# SpringReverbRev2_1_SMD.net
KiCad netlist of a schematic drawn in EAGLE
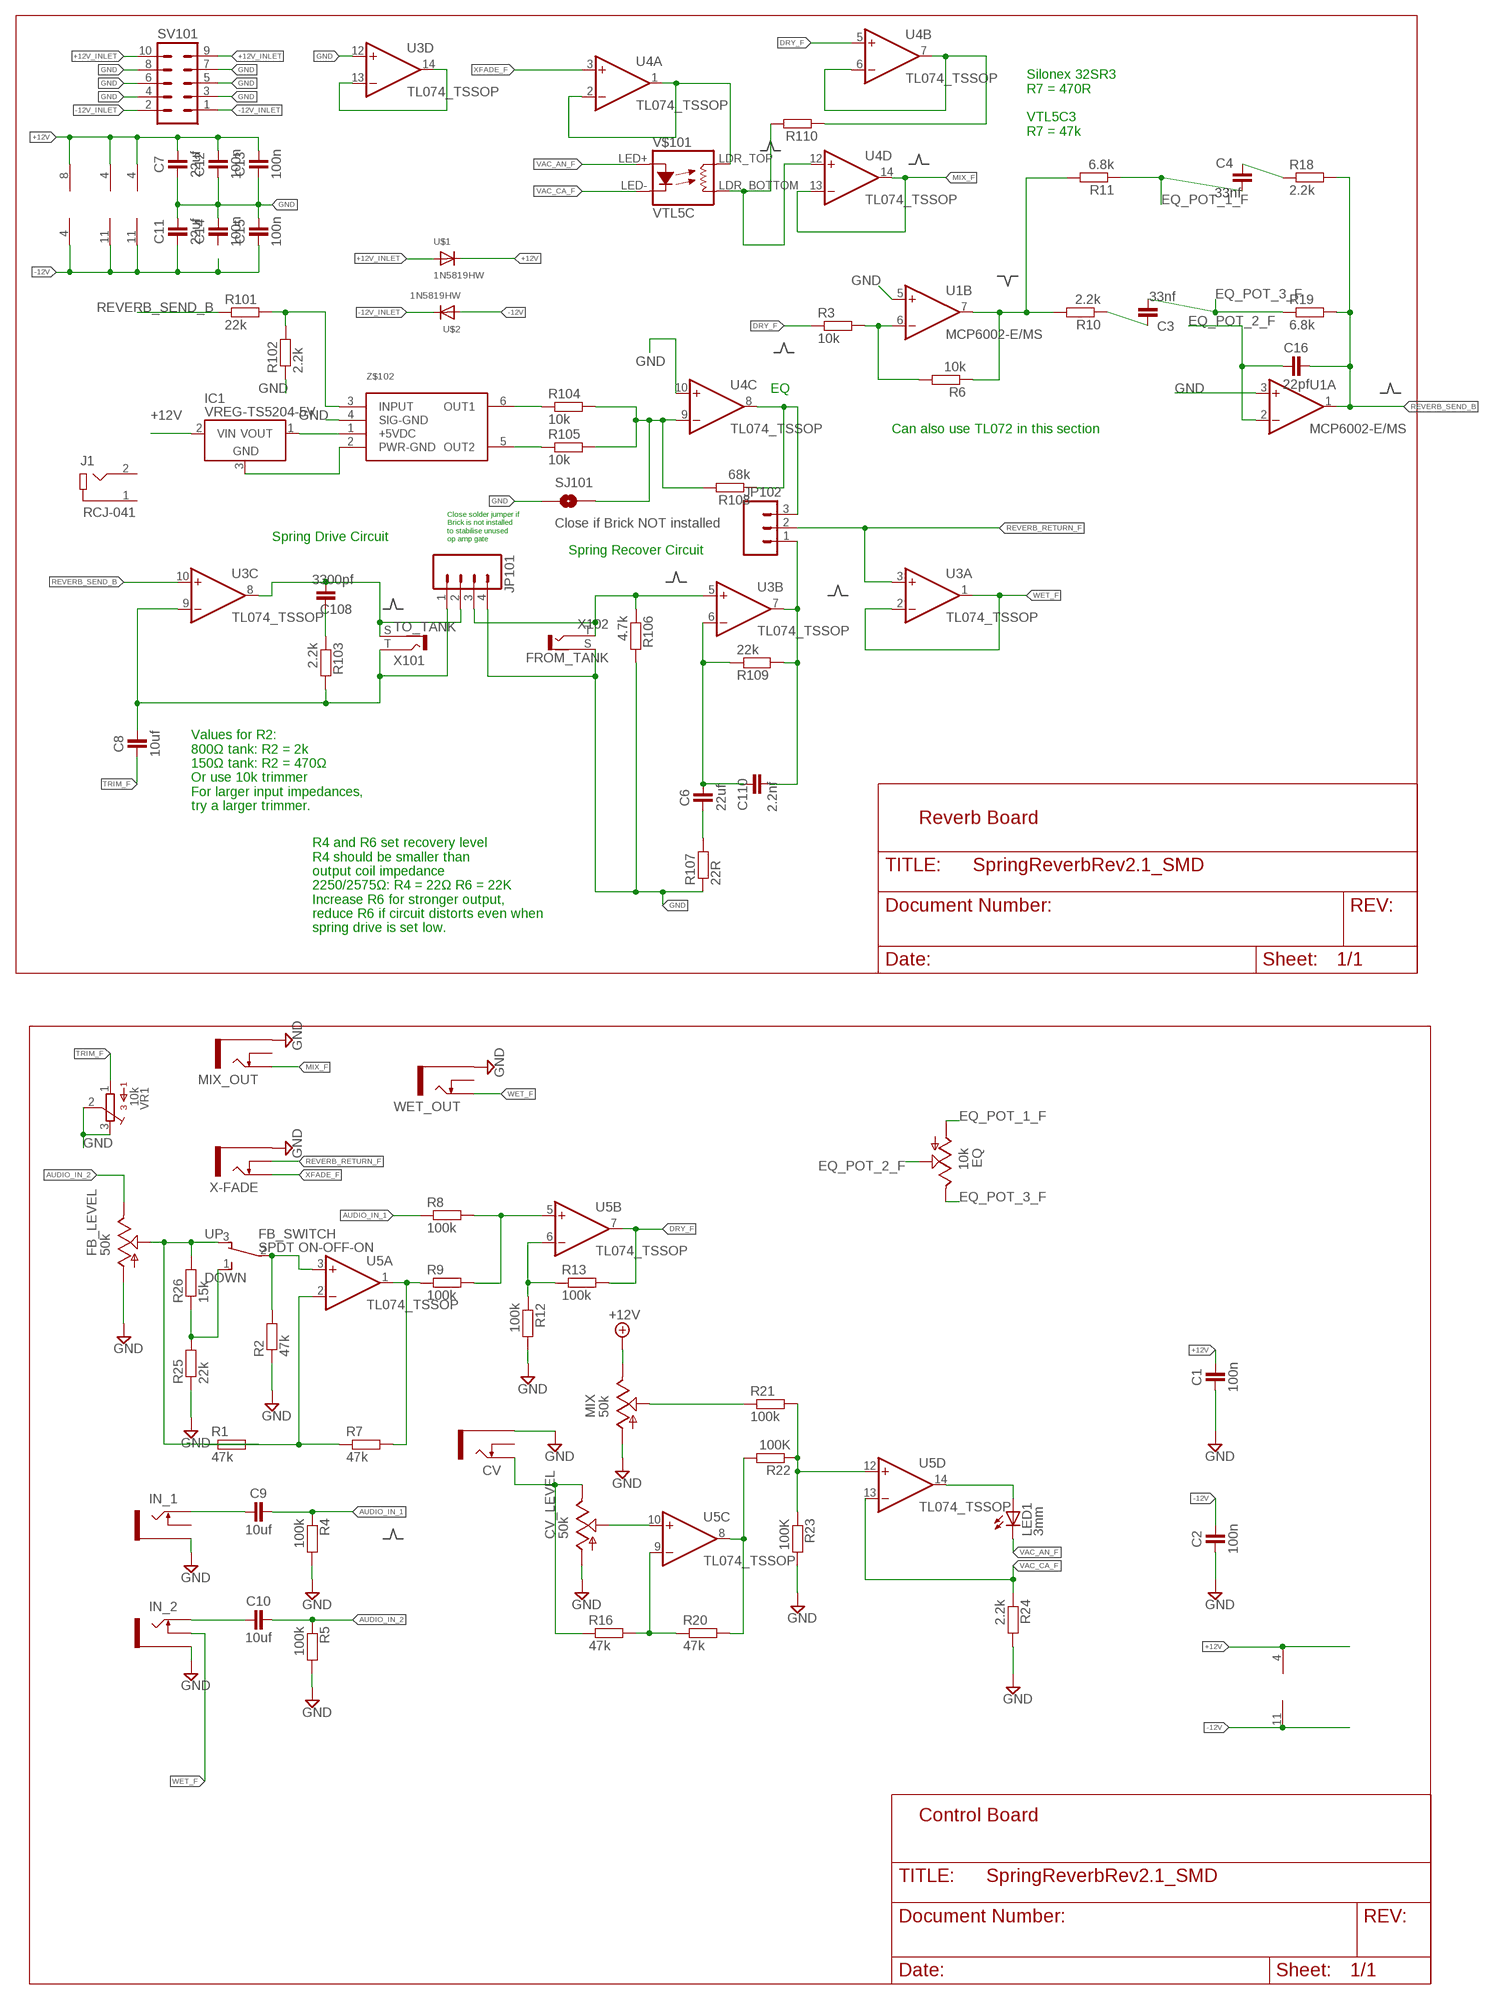
[diagram p0: schematic, sheet 1]

(export (version "E")
  (design (tool "Eeschema 10.0.6"))
  (components
    (comp (ref "C1")
      (value "100n")
      (footprint "eagle-import:C0402")
      (libsource (lib "eagle-import") (part "CAPACITOR-0402"))
    )
    (comp (ref "C2")
      (value "100n")
      (footprint "eagle-import:C0402")
      (libsource (lib "eagle-import") (part "CAPACITOR-0402"))
    )
    (comp (ref "C3")
      (value "33nf")
      (footprint "eagle-import:C0402")
      (libsource (lib "eagle-import") (part "CAPACITOR-0402"))
    )
    (comp (ref "C4")
      (value "33nf")
      (footprint "eagle-import:C0402")
      (libsource (lib "eagle-import") (part "CAPACITOR-0402"))
    )
    (comp (ref "C6")
      (value "22uf")
      (footprint "eagle-import:C1210")
      (libsource (lib "eagle-import") (part "CAPACITOR-1210"))
    )
    (comp (ref "C7")
      (value "22uf")
      (footprint "eagle-import:C1206")
      (libsource (lib "eagle-import") (part "CAPACITOR-1206"))
    )
    (comp (ref "C8")
      (value "10uf")
      (footprint "eagle-import:C0805")
      (libsource (lib "eagle-import") (part "CAPACITOR-0805"))
    )
    (comp (ref "C9")
      (value "10uf")
      (footprint "eagle-import:C0805")
      (libsource (lib "eagle-import") (part "CAPACITOR-0805"))
    )
    (comp (ref "C10")
      (value "10uf")
      (footprint "eagle-import:C0805")
      (libsource (lib "eagle-import") (part "CAPACITOR-0805"))
    )
    (comp (ref "C11")
      (value "22uf")
      (footprint "eagle-import:C1206")
      (libsource (lib "eagle-import") (part "CAPACITOR-1206"))
    )
    (comp (ref "C12")
      (value "100n")
      (footprint "eagle-import:C0402")
      (libsource (lib "eagle-import") (part "CAPACITOR-0402"))
    )
    (comp (ref "C13")
      (value "100n")
      (footprint "eagle-import:C0402")
      (libsource (lib "eagle-import") (part "CAPACITOR-0402"))
    )
    (comp (ref "C14")
      (value "100n")
      (footprint "eagle-import:C0402")
      (libsource (lib "eagle-import") (part "CAPACITOR-0402"))
    )
    (comp (ref "C15")
      (value "100n")
      (footprint "eagle-import:C0402")
      (libsource (lib "eagle-import") (part "CAPACITOR-0402"))
    )
    (comp (ref "C16")
      (value "22pf")
      (footprint "eagle-import:C0402")
      (libsource (lib "eagle-import") (part "CAPACITOR-0402"))
    )
    (comp (ref "C108")
      (value "3300pf")
      (footprint "eagle-import:C0402")
      (libsource (lib "eagle-import") (part "CAPACITOR-0402"))
    )
    (comp (ref "C110")
      (value "2.2nf")
      (footprint "eagle-import:C0402")
      (libsource (lib "eagle-import") (part "CAPACITOR-0402"))
    )
    (comp (ref "CV")
      (value "THONKICONNNEW")
      (footprint "eagle-import:WQP-PJ301M-12_JACK")
      (libsource (lib "eagle-import") (part "THONKICONNNEW"))
    )
    (comp (ref "CV_LEVEL")
      (value "50k")
      (footprint "eagle-import:EVUF")
      (libsource (lib "eagle-import") (part "ALPHA-9MMAF2"))
    )
    (comp (ref "EQ")
      (value "10k")
      (footprint "eagle-import:EVUF")
      (libsource (lib "eagle-import") (part "ALPHA-9MMAF2"))
    )
    (comp (ref "FB_LEVEL")
      (value "50k")
      (footprint "eagle-import:EVUF")
      (libsource (lib "eagle-import") (part "ALPHA-9MMAF2"))
    )
    (comp (ref "FB_SWITCH")
      (value "SPDT ON-OFF-ON")
      (footprint "eagle-import:SPDT-VERTICAL-TOP-SUBMINI-MULTICOMP")
      (libsource (lib "eagle-import") (part "SPDT-VERTICAL-UPTOP-SUBMINI"))
    )
    (comp (ref "IC1")
      (value "VREG-TS5204-5V")
      (footprint "eagle-import:SOT23")
      (libsource (lib "eagle-import") (part "VREG-TS5204-5V"))
    )
    (comp (ref "IN_1")
      (value "THONKICONNNEW")
      (footprint "eagle-import:WQP-PJ301M-12_JACK")
      (libsource (lib "eagle-import") (part "THONKICONNNEW"))
    )
    (comp (ref "IN_2")
      (value "THONKICONNNEW")
      (footprint "eagle-import:WQP-PJ301M-12_JACK")
      (libsource (lib "eagle-import") (part "THONKICONNNEW"))
    )
    (comp (ref "J1")
      (value "RCJ-041")
      (footprint "eagle-import:RCJ-041")
      (fields
        (field (name "DIGIKEY_PART_NUMBER") "CP-1418-ND")
        (field (name "MANUFACTURER") "CUI Inc.")
        (field (name "CREATED_BY") "PCBLayout.com")
      )
      (libsource (lib "eagle-import") (part "RCJ-041"))
    )
    (comp (ref "JP101")
      (value "M04POLAR")
      (footprint "eagle-import:MOLEX-1X4")
      (libsource (lib "eagle-import") (part "M04POLAR"))
    )
    (comp (ref "JP102")
      (value "M03LOCK_NO_SILK")
      (footprint "eagle-import:1X03_LOCK_NO_SILK")
      (libsource (lib "eagle-import") (part "M03LOCK_NO_SILK"))
    )
    (comp (ref "LED1")
      (value "3mm")
      (footprint "eagle-import:LED3MM")
      (libsource (lib "eagle-import") (part "LED3MM"))
    )
    (comp (ref "MIX")
      (value "50k")
      (footprint "eagle-import:EVUF")
      (libsource (lib "eagle-import") (part "ALPHA-9MMAF2"))
    )
    (comp (ref "MIX_OUT")
      (value "THONKICONNNEW")
      (footprint "eagle-import:WQP-PJ301M-12_JACK")
      (libsource (lib "eagle-import") (part "THONKICONNNEW"))
    )
    (comp (ref "R1")
      (value "47k")
      (footprint "eagle-import:C0402")
      (libsource (lib "eagle-import") (part "RESISTOR-0402"))
    )
    (comp (ref "R2")
      (value "47k")
      (footprint "eagle-import:C0402")
      (libsource (lib "eagle-import") (part "RESISTOR-0402"))
    )
    (comp (ref "R3")
      (value "10k")
      (footprint "eagle-import:C0402")
      (libsource (lib "eagle-import") (part "RESISTOR-0402"))
    )
    (comp (ref "R4")
      (value "100k")
      (footprint "eagle-import:C0402")
      (libsource (lib "eagle-import") (part "RESISTOR-0402"))
    )
    (comp (ref "R5")
      (value "100k")
      (footprint "eagle-import:C0402")
      (libsource (lib "eagle-import") (part "RESISTOR-0402"))
    )
    (comp (ref "R6")
      (value "10k")
      (footprint "eagle-import:C0402")
      (libsource (lib "eagle-import") (part "RESISTOR-0402"))
    )
    (comp (ref "R7")
      (value "47k")
      (footprint "eagle-import:C0402")
      (libsource (lib "eagle-import") (part "RESISTOR-0402"))
    )
    (comp (ref "R8")
      (value "100k")
      (footprint "eagle-import:C0402")
      (libsource (lib "eagle-import") (part "RESISTOR-0402"))
    )
    (comp (ref "R9")
      (value "100k")
      (footprint "eagle-import:C0402")
      (libsource (lib "eagle-import") (part "RESISTOR-0402"))
    )
    (comp (ref "R10")
      (value "2.2k")
      (footprint "eagle-import:C0402")
      (libsource (lib "eagle-import") (part "RESISTOR-0402"))
    )
    (comp (ref "R11")
      (value "6.8k")
      (footprint "eagle-import:C0402")
      (libsource (lib "eagle-import") (part "RESISTOR-0402"))
    )
    (comp (ref "R12")
      (value "100k")
      (footprint "eagle-import:C0402")
      (libsource (lib "eagle-import") (part "RESISTOR-0402"))
    )
    (comp (ref "R13")
      (value "100k")
      (footprint "eagle-import:C0402")
      (libsource (lib "eagle-import") (part "RESISTOR-0402"))
    )
    (comp (ref "R16")
      (value "47k")
      (footprint "eagle-import:C0402")
      (libsource (lib "eagle-import") (part "RESISTOR-0402"))
    )
    (comp (ref "R18")
      (value "2.2k")
      (footprint "eagle-import:C0402")
      (libsource (lib "eagle-import") (part "RESISTOR-0402"))
    )
    (comp (ref "R19")
      (value "6.8k")
      (footprint "eagle-import:C0402")
      (libsource (lib "eagle-import") (part "RESISTOR-0402"))
    )
    (comp (ref "R20")
      (value "47k")
      (footprint "eagle-import:C0402")
      (libsource (lib "eagle-import") (part "RESISTOR-0402"))
    )
    (comp (ref "R21")
      (value "100k")
      (footprint "eagle-import:C0402")
      (libsource (lib "eagle-import") (part "RESISTOR-0402"))
    )
    (comp (ref "R22")
      (value "100K")
      (footprint "eagle-import:C0402")
      (libsource (lib "eagle-import") (part "RESISTOR-0402"))
    )
    (comp (ref "R23")
      (value "100K")
      (footprint "eagle-import:C0402")
      (libsource (lib "eagle-import") (part "RESISTOR-0402"))
    )
    (comp (ref "R24")
      (value "2.2k")
      (footprint "eagle-import:C0402")
      (libsource (lib "eagle-import") (part "RESISTOR-0402"))
    )
    (comp (ref "R25")
      (value "22k")
      (footprint "eagle-import:C0402")
      (libsource (lib "eagle-import") (part "RESISTOR-0402"))
    )
    (comp (ref "R26")
      (value "15k")
      (footprint "eagle-import:C0402")
      (libsource (lib "eagle-import") (part "RESISTOR-0402"))
    )
    (comp (ref "R101")
      (value "22k")
      (footprint "eagle-import:C0402")
      (libsource (lib "eagle-import") (part "RESISTOR-0402"))
    )
    (comp (ref "R102")
      (value "2.2k")
      (footprint "eagle-import:C0402")
      (libsource (lib "eagle-import") (part "RESISTOR-0402"))
    )
    (comp (ref "R103")
      (value "2.2k")
      (footprint "eagle-import:C0402")
      (libsource (lib "eagle-import") (part "RESISTOR-0402"))
    )
    (comp (ref "R104")
      (value "10k")
      (footprint "eagle-import:C0402")
      (libsource (lib "eagle-import") (part "RESISTOR-0402"))
    )
    (comp (ref "R105")
      (value "10k")
      (footprint "eagle-import:C0402")
      (libsource (lib "eagle-import") (part "RESISTOR-0402"))
    )
    (comp (ref "R106")
      (value "4.7k")
      (footprint "eagle-import:C0402")
      (libsource (lib "eagle-import") (part "RESISTOR-0402"))
    )
    (comp (ref "R107")
      (value "22R")
      (footprint "eagle-import:C0402")
      (libsource (lib "eagle-import") (part "RESISTOR-0402"))
    )
    (comp (ref "R108")
      (value "68k")
      (footprint "eagle-import:C0402")
      (libsource (lib "eagle-import") (part "RESISTOR-0402"))
    )
    (comp (ref "R109")
      (value "22k")
      (footprint "eagle-import:C0402")
      (libsource (lib "eagle-import") (part "RESISTOR-0402"))
    )
    (comp (ref "R110")
      (value "RESISTOR-0402")
      (footprint "eagle-import:C0402")
      (libsource (lib "eagle-import") (part "RESISTOR-0402"))
    )
    (comp (ref "SJ101")
      (value "Close if Brick NOT installed")
      (footprint "eagle-import:SJ_2S-NOTRACE")
      (libsource (lib "eagle-import") (part "SOLDERJUMPERNC2"))
    )
    (comp (ref "SV101")
      (value "10_PIN_HEADER")
      (footprint "eagle-import:MA05-2")
      (libsource (lib "eagle-import") (part "10_PIN_HEADER"))
    )
    (comp (ref "U$1")
      (value "1N5819HW")
      (footprint "eagle-import:SOD-123-EDITED")
      (libsource (lib "eagle-import") (part "1N5819HW"))
    )
    (comp (ref "U$2")
      (value "1N5819HW")
      (footprint "eagle-import:SOD-123-EDITED")
      (libsource (lib "eagle-import") (part "1N5819HW"))
    )
    (comp (ref "U1")
      (value "MCP6002-E/MS")
      (footprint "eagle-import:SOP65P490X110-8N")
      (libsource (lib "eagle-import") (part "MCP6002-E/MS"))
    )
    (comp (ref "U3")
      (value "TL074_TSSOP")
      (footprint "eagle-import:SOP65P640X120-14N")
      (fields (field (name "MPN") "MCP6004-I/ST"))
      (libsource (lib "eagle-import") (part "LM324_TSSOP"))
    )
    (comp (ref "U4")
      (value "TL074_TSSOP")
      (footprint "eagle-import:SOP65P640X120-14N")
      (fields (field (name "MPN") "MCP6004-I/ST"))
      (libsource (lib "eagle-import") (part "LM324_TSSOP"))
    )
    (comp (ref "U5")
      (value "TL074_TSSOP")
      (footprint "eagle-import:SOP65P640X120-14N")
      (fields (field (name "MPN") "MCP6004-I/ST"))
      (libsource (lib "eagle-import") (part "LM324_TSSOP"))
    )
    (comp (ref "V$101")
      (value "VTL5C")
      (footprint "eagle-import:VACTROL_COMPACT")
      (libsource (lib "eagle-import") (part "VACTROL_COMPACT"))
    )
    (comp (ref "VR1")
      (value "10k")
      (footprint "eagle-import:BOURNS_3362P_TRIMMER")
      (libsource (lib "eagle-import") (part "BOURNS_3362P_TRIMMERP"))
    )
    (comp (ref "WET_OUT")
      (value "THONKICONNNEW")
      (footprint "eagle-import:WQP-PJ301M-12_JACK")
      (libsource (lib "eagle-import") (part "THONKICONNNEW"))
    )
    (comp (ref "X-FADE")
      (value "THONKICONNNEW")
      (footprint "eagle-import:WQP-PJ301M-12_JACK")
      (libsource (lib "eagle-import") (part "THONKICONNNEW"))
    )
    (comp (ref "X101")
      (value "TO_TANK")
      (footprint "eagle-import:BTOR1")
      (fields (field (name "MPN") "BTOR 1"))
      (libsource (lib "eagle-import") (part "BTOR1"))
    )
    (comp (ref "X102")
      (value "FROM_TANK")
      (footprint "eagle-import:BTOR1")
      (fields (field (name "MPN") "BTOR 1"))
      (libsource (lib "eagle-import") (part "BTOR1"))
    )
    (comp (ref "Z$102")
      (value "BTDR-2H")
      (footprint "eagle-import:BTDR-2H")
      (libsource (lib "eagle-import") (part "BTDR-2H"))
    )
  )
  (nets
    (net (code "1") (name "+12V") (class "Default")
      (node (ref "C1") (pin "2") (pinfunction "2_2") (pintype "passive"))
      (node (ref "C12") (pin "2") (pinfunction "2_2") (pintype "passive"))
      (node (ref "C13") (pin "2") (pinfunction "2_2") (pintype "passive"))
      (node (ref "C7") (pin "2") (pinfunction "2_2") (pintype "passive"))
      (node (ref "IC1") (pin "2") (pinfunction "VIN_2") (pintype "power_in"))
      (node (ref "MIX") (pin "3") (pinfunction "E_3") (pintype "passive"))
      (node (ref "U$1") (pin "C") (pinfunction "C_C") (pintype "passive"))
      (node (ref "U1") (pin "8") (pinfunction "V+_8") (pintype "power_in"))
      (node (ref "U3") (pin "4") (pinfunction "V+_4") (pintype "power_in"))
      (node (ref "U4") (pin "4") (pinfunction "V+_4") (pintype "power_in"))
      (node (ref "U5") (pin "4") (pinfunction "V+_4") (pintype "power_in"))
    )
    (net (code "2") (name "+12V_INLET") (class "Default")
      (node (ref "SV101") (pin "10") (pinfunction "10_10") (pintype "passive"))
      (node (ref "SV101") (pin "9") (pinfunction "9_9") (pintype "passive"))
      (node (ref "U$1") (pin "A") (pinfunction "A_A") (pintype "passive"))
    )
    (net (code "3") (name "-12V") (class "Default")
      (node (ref "C11") (pin "1") (pinfunction "1_1") (pintype "passive"))
      (node (ref "C15") (pin "1") (pinfunction "1_1") (pintype "passive"))
      (node (ref "C2") (pin "2") (pinfunction "2_2") (pintype "passive"))
      (node (ref "U$2") (pin "A") (pinfunction "A_A") (pintype "passive"))
      (node (ref "U1") (pin "4") (pinfunction "V-_4") (pintype "power_in"))
      (node (ref "U3") (pin "11") (pinfunction "V-_11") (pintype "power_in"))
      (node (ref "U4") (pin "11") (pinfunction "V-_11") (pintype "power_in"))
      (node (ref "U5") (pin "11") (pinfunction "V-_11") (pintype "power_in"))
    )
    (net (code "4") (name "-12V_INLET") (class "Default")
      (node (ref "SV101") (pin "1") (pinfunction "1_1") (pintype "passive"))
      (node (ref "SV101") (pin "2") (pinfunction "2_2") (pintype "passive"))
      (node (ref "U$2") (pin "C") (pinfunction "C_C") (pintype "passive"))
    )
    (net (code "5") (name "/EQ_POT_1_F") (class "Default")
      (node (ref "C4") (pin "2") (pinfunction "2_2") (pintype "passive"))
      (node (ref "EQ") (pin "1") (pinfunction "A_1") (pintype "passive"))
      (node (ref "R11") (pin "1") (pinfunction "1_1") (pintype "passive"))
    )
    (net (code "6") (name "/EQ_POT_2_F") (class "Default")
      (node (ref "C16") (pin "1") (pinfunction "1_1") (pintype "passive"))
      (node (ref "EQ") (pin "2") (pinfunction "S_2") (pintype "passive"))
      (node (ref "U1") (pin "2") (pinfunction "-IN_2") (pintype "input"))
    )
    (net (code "7") (name "/EQ_POT_3_F") (class "Default")
      (node (ref "C3") (pin "2") (pinfunction "2_2") (pintype "passive"))
      (node (ref "EQ") (pin "3") (pinfunction "E_3") (pintype "passive"))
      (node (ref "R19") (pin "1") (pinfunction "1_1") (pintype "passive"))
    )
    (net (code "8") (name "AUDIO_IN_1") (class "Default")
      (node (ref "C9") (pin "2") (pinfunction "2_2") (pintype "passive"))
      (node (ref "R4") (pin "1") (pinfunction "1_1") (pintype "passive"))
      (node (ref "R8") (pin "1") (pinfunction "1_1") (pintype "passive"))
    )
    (net (code "9") (name "AUDIO_IN_2") (class "Default")
      (node (ref "C10") (pin "2") (pinfunction "2_2") (pintype "passive"))
      (node (ref "FB_LEVEL") (pin "3") (pinfunction "E_3") (pintype "passive"))
      (node (ref "R5") (pin "1") (pinfunction "1_1") (pintype "passive"))
    )
    (net (code "10") (name "DRY_F") (class "Default")
      (node (ref "R13") (pin "2") (pinfunction "2_2") (pintype "passive"))
      (node (ref "R3") (pin "1") (pinfunction "1_1") (pintype "passive"))
      (node (ref "U4") (pin "5") (pinfunction "+IN_5") (pintype "input"))
      (node (ref "U5") (pin "7") (pinfunction "OUT_7") (pintype "output"))
    )
    (net (code "11") (name "GND") (class "Default")
      (node (ref "C1") (pin "1") (pinfunction "1_1") (pintype "passive"))
      (node (ref "C11") (pin "2") (pinfunction "2_2") (pintype "passive"))
      (node (ref "C12") (pin "1") (pinfunction "1_1") (pintype "passive"))
      (node (ref "C13") (pin "1") (pinfunction "1_1") (pintype "passive"))
      (node (ref "C14") (pin "2") (pinfunction "2_2") (pintype "passive"))
      (node (ref "C15") (pin "2") (pinfunction "2_2") (pintype "passive"))
      (node (ref "C2") (pin "1") (pinfunction "1_1") (pintype "passive"))
      (node (ref "C7") (pin "1") (pinfunction "1_1") (pintype "passive"))
      (node (ref "CV") (pin "P$3_SLEEVE") (pinfunction "SLEEVE_P$3_SLEEVE") (pintype "passive"))
      (node (ref "CV_LEVEL") (pin "1") (pinfunction "A_1") (pintype "passive"))
      (node (ref "FB_LEVEL") (pin "1") (pinfunction "A_1") (pintype "passive"))
      (node (ref "IN_1") (pin "P$3_SLEEVE") (pinfunction "SLEEVE_P$3_SLEEVE") (pintype "passive"))
      (node (ref "IN_2") (pin "P$3_SLEEVE") (pinfunction "SLEEVE_P$3_SLEEVE") (pintype "passive"))
      (node (ref "JP101") (pin "4") (pinfunction "4_4") (pintype "passive"))
      (node (ref "MIX") (pin "1") (pinfunction "A_1") (pintype "passive"))
      (node (ref "MIX_OUT") (pin "P$3_SLEEVE") (pinfunction "SLEEVE_P$3_SLEEVE") (pintype "passive"))
      (node (ref "R102") (pin "1") (pinfunction "1_1") (pintype "passive"))
      (node (ref "R106") (pin "2") (pinfunction "2_2") (pintype "passive"))
      (node (ref "R107") (pin "1") (pinfunction "1_1") (pintype "passive"))
      (node (ref "R12") (pin "2") (pinfunction "2_2") (pintype "passive"))
      (node (ref "R2") (pin "1") (pinfunction "1_1") (pintype "passive"))
      (node (ref "R23") (pin "2") (pinfunction "2_2") (pintype "passive"))
      (node (ref "R24") (pin "2") (pinfunction "2_2") (pintype "passive"))
      (node (ref "R25") (pin "1") (pinfunction "1_1") (pintype "passive"))
      (node (ref "R4") (pin "2") (pinfunction "2_2") (pintype "passive"))
      (node (ref "R5") (pin "2") (pinfunction "2_2") (pintype "passive"))
      (node (ref "SJ101") (pin "1") (pinfunction "1_1") (pintype "passive"))
      (node (ref "SV101") (pin "3") (pinfunction "3_3") (pintype "passive"))
      (node (ref "SV101") (pin "4") (pinfunction "4_4") (pintype "passive"))
      (node (ref "SV101") (pin "5") (pinfunction "5_5") (pintype "passive"))
      (node (ref "SV101") (pin "6") (pinfunction "6_6") (pintype "passive"))
      (node (ref "SV101") (pin "7") (pinfunction "7_7") (pintype "passive"))
      (node (ref "SV101") (pin "8") (pinfunction "8_8") (pintype "passive"))
      (node (ref "U1") (pin "3") (pinfunction "+IN_3") (pintype "input"))
      (node (ref "U1") (pin "5") (pinfunction "+IN_5") (pintype "input"))
      (node (ref "U3") (pin "12") (pinfunction "+IN_12") (pintype "input"))
      (node (ref "U4") (pin "10") (pinfunction "+IN_10") (pintype "input"))
      (node (ref "VR1") (pin "2") (pinfunction "2_2") (pintype "passive"))
      (node (ref "VR1") (pin "3") (pinfunction "3_3") (pintype "passive"))
      (node (ref "WET_OUT") (pin "P$3_SLEEVE") (pinfunction "SLEEVE_P$3_SLEEVE") (pintype "passive"))
      (node (ref "X-FADE") (pin "P$3_SLEEVE") (pinfunction "SLEEVE_P$3_SLEEVE") (pintype "passive"))
      (node (ref "X102") (pin "S") (pinfunction "2_S") (pintype "passive"))
      (node (ref "Z$102") (pin "4") (pinfunction "SIG-GND_4") (pintype "bidirectional"))
    )
    (net (code "12") (name "MIX_F") (class "Default")
      (node (ref "MIX_OUT") (pin "P$1_TIP") (pinfunction "TIP_P$1_TIP") (pintype "passive"))
      (node (ref "U4") (pin "13") (pinfunction "-IN_13") (pintype "input"))
      (node (ref "U4") (pin "14") (pinfunction "OUT_14") (pintype "output"))
    )
    (net (code "13") (name "Net-(C3-Pad1)") (class "Default")
      (node (ref "C3") (pin "1") (pinfunction "1_1") (pintype "passive"))
      (node (ref "R10") (pin "1") (pinfunction "1_1") (pintype "passive"))
    )
    (net (code "14") (name "Net-(C4-Pad1)") (class "Default")
      (node (ref "C4") (pin "1") (pinfunction "1_1") (pintype "passive"))
      (node (ref "R18") (pin "1") (pinfunction "1_1") (pintype "passive"))
    )
    (net (code "15") (name "Net-(C6-Pad1)") (class "Default")
      (node (ref "C6") (pin "1") (pinfunction "1_1") (pintype "passive"))
      (node (ref "R107") (pin "2") (pinfunction "2_2") (pintype "passive"))
    )
    (net (code "16") (name "Net-(C108-Pad1)") (class "Default")
      (node (ref "C108") (pin "1") (pinfunction "1_1") (pintype "passive"))
      (node (ref "R103") (pin "1") (pinfunction "1_1") (pintype "passive"))
    )
    (net (code "17") (name "Net-(CV-TIP)") (class "Default")
      (node (ref "CV") (pin "P$1_TIP") (pinfunction "TIP_P$1_TIP") (pintype "passive"))
      (node (ref "CV_LEVEL") (pin "3") (pinfunction "E_3") (pintype "passive"))
      (node (ref "R16") (pin "1") (pinfunction "1_1") (pintype "passive"))
    )
    (net (code "18") (name "Net-(CV_LEVEL-S)") (class "Default")
      (node (ref "CV_LEVEL") (pin "2") (pinfunction "S_2") (pintype "passive"))
      (node (ref "U5") (pin "10") (pinfunction "+IN_10") (pintype "input"))
    )
    (net (code "19") (name "Net-(FB_LEVEL-S)") (class "Default")
      (node (ref "FB_LEVEL") (pin "2") (pinfunction "S_2") (pintype "passive"))
      (node (ref "FB_SWITCH") (pin "3") (pinfunction "3_3") (pintype "passive"))
      (node (ref "R1") (pin "2") (pinfunction "2_2") (pintype "passive"))
      (node (ref "R26") (pin "2") (pinfunction "2_2") (pintype "passive"))
    )
    (net (code "20") (name "Net-(FB_SWITCH-Pad1)") (class "Default")
      (node (ref "FB_SWITCH") (pin "1") (pinfunction "1_1") (pintype "passive"))
      (node (ref "R25") (pin "2") (pinfunction "2_2") (pintype "passive"))
      (node (ref "R26") (pin "1") (pinfunction "1_1") (pintype "passive"))
    )
    (net (code "21") (name "Net-(IC1-GND)") (class "Default")
      (node (ref "IC1") (pin "3") (pinfunction "GND_3") (pintype "power_in"))
      (node (ref "Z$102") (pin "2") (pinfunction "PWR-GND_2") (pintype "bidirectional"))
    )
    (net (code "22") (name "Net-(IC1-VOUT)") (class "Default")
      (node (ref "IC1") (pin "1") (pinfunction "VOUT_1") (pintype "power_in"))
      (node (ref "Z$102") (pin "1") (pinfunction "+5VDC_1") (pintype "bidirectional"))
    )
    (net (code "23") (name "Net-(IN_1-TIP)") (class "Default")
      (node (ref "C9") (pin "1") (pinfunction "1_1") (pintype "passive"))
      (node (ref "IN_1") (pin "P$1_TIP") (pinfunction "TIP_P$1_TIP") (pintype "passive"))
    )
    (net (code "24") (name "Net-(IN_2-TIP)") (class "Default")
      (node (ref "C10") (pin "1") (pinfunction "1_1") (pintype "passive"))
      (node (ref "IN_2") (pin "P$1_TIP") (pinfunction "TIP_P$1_TIP") (pintype "passive"))
    )
    (net (code "25") (name "Net-(MIX-S)") (class "Default")
      (node (ref "MIX") (pin "2") (pinfunction "S_2") (pintype "passive"))
      (node (ref "R21") (pin "1") (pinfunction "1_1") (pintype "passive"))
    )
    (net (code "26") (name "Net-(U1B--IN)") (class "Default")
      (node (ref "R3") (pin "2") (pinfunction "2_2") (pintype "passive"))
      (node (ref "R6") (pin "2") (pinfunction "2_2") (pintype "passive"))
      (node (ref "U1") (pin "6") (pinfunction "-IN_6") (pintype "input"))
    )
    (net (code "27") (name "Net-(U1B-OUT)") (class "Default")
      (node (ref "R10") (pin "2") (pinfunction "2_2") (pintype "passive"))
      (node (ref "R11") (pin "2") (pinfunction "2_2") (pintype "passive"))
      (node (ref "R6") (pin "1") (pinfunction "1_1") (pintype "passive"))
      (node (ref "U1") (pin "7") (pinfunction "OUT_7") (pintype "output"))
    )
    (net (code "28") (name "Net-(U3B-+IN)") (class "Default")
      (node (ref "JP101") (pin "3") (pinfunction "3_3") (pintype "passive"))
      (node (ref "R106") (pin "1") (pinfunction "1_1") (pintype "passive"))
      (node (ref "U3") (pin "5") (pinfunction "+IN_5") (pintype "input"))
      (node (ref "X102") (pin "T") (pinfunction "1_T") (pintype "passive"))
    )
    (net (code "29") (name "Net-(U3B--IN)") (class "Default")
      (node (ref "C110") (pin "1") (pinfunction "1_1") (pintype "passive"))
      (node (ref "C6") (pin "2") (pinfunction "2_2") (pintype "passive"))
      (node (ref "R109") (pin "1") (pinfunction "1_1") (pintype "passive"))
      (node (ref "U3") (pin "6") (pinfunction "-IN_6") (pintype "input"))
    )
    (net (code "30") (name "Net-(U3B-OUT)") (class "Default")
      (node (ref "C110") (pin "2") (pinfunction "2_2") (pintype "passive"))
      (node (ref "JP102") (pin "1") (pinfunction "1_1") (pintype "passive"))
      (node (ref "R109") (pin "2") (pinfunction "2_2") (pintype "passive"))
      (node (ref "U3") (pin "7") (pinfunction "OUT_7") (pintype "output"))
    )
    (net (code "31") (name "Net-(U3C--IN)") (class "Default")
      (node (ref "C8") (pin "2") (pinfunction "2_2") (pintype "passive"))
      (node (ref "JP101") (pin "1") (pinfunction "1_1") (pintype "passive"))
      (node (ref "R103") (pin "2") (pinfunction "2_2") (pintype "passive"))
      (node (ref "U3") (pin "9") (pinfunction "-IN_9") (pintype "input"))
      (node (ref "X101") (pin "T") (pinfunction "1_T") (pintype "passive"))
    )
    (net (code "32") (name "Net-(U3C-OUT)") (class "Default")
      (node (ref "C108") (pin "2") (pinfunction "2_2") (pintype "passive"))
      (node (ref "JP101") (pin "2") (pinfunction "2_2") (pintype "passive"))
      (node (ref "U3") (pin "8") (pinfunction "OUT_8") (pintype "output"))
      (node (ref "X101") (pin "S") (pinfunction "2_S") (pintype "passive"))
    )
    (net (code "33") (name "Net-(U3D--IN)") (class "Default")
      (node (ref "U3") (pin "13") (pinfunction "-IN_13") (pintype "input"))
      (node (ref "U3") (pin "14") (pinfunction "OUT_14") (pintype "output"))
    )
    (net (code "34") (name "Net-(U4A--IN)") (class "Default")
      (node (ref "U4") (pin "1") (pinfunction "OUT_1") (pintype "output"))
      (node (ref "U4") (pin "2") (pinfunction "-IN_2") (pintype "input"))
      (node (ref "V$101") (pin "LDR_TOP") (pinfunction "RES1_LDR_TOP") (pintype "passive"))
    )
    (net (code "35") (name "Net-(U4B--IN)") (class "Default")
      (node (ref "R110") (pin "1") (pinfunction "1_1") (pintype "passive"))
      (node (ref "U4") (pin "6") (pinfunction "-IN_6") (pintype "input"))
      (node (ref "U4") (pin "7") (pinfunction "OUT_7") (pintype "output"))
    )
    (net (code "36") (name "Net-(U4C--IN)") (class "Default")
      (node (ref "R104") (pin "2") (pinfunction "2_2") (pintype "passive"))
      (node (ref "R105") (pin "2") (pinfunction "2_2") (pintype "passive"))
      (node (ref "R108") (pin "2") (pinfunction "2_2") (pintype "passive"))
      (node (ref "SJ101") (pin "2") (pinfunction "2_2") (pintype "passive"))
      (node (ref "U4") (pin "9") (pinfunction "-IN_9") (pintype "input"))
    )
    (net (code "37") (name "Net-(U4C-OUT)") (class "Default")
      (node (ref "JP102") (pin "3") (pinfunction "3_3") (pintype "passive"))
      (node (ref "R108") (pin "1") (pinfunction "1_1") (pintype "passive"))
      (node (ref "U4") (pin "8") (pinfunction "OUT_8") (pintype "output"))
    )
    (net (code "38") (name "Net-(U4D-+IN)") (class "Default")
      (node (ref "R110") (pin "2") (pinfunction "2_2") (pintype "passive"))
      (node (ref "U4") (pin "12") (pinfunction "+IN_12") (pintype "input"))
      (node (ref "V$101") (pin "LDR_BOTTOM") (pinfunction "RES2_LDR_BOTTOM") (pintype "passive"))
    )
    (net (code "39") (name "Net-(U5A-+IN)") (class "Default")
      (node (ref "FB_SWITCH") (pin "2") (pinfunction "2_2") (pintype "passive"))
      (node (ref "R2") (pin "2") (pinfunction "2_2") (pintype "passive"))
      (node (ref "U5") (pin "3") (pinfunction "+IN_3") (pintype "input"))
    )
    (net (code "40") (name "Net-(U5A--IN)") (class "Default")
      (node (ref "R1") (pin "1") (pinfunction "1_1") (pintype "passive"))
      (node (ref "R7") (pin "1") (pinfunction "1_1") (pintype "passive"))
      (node (ref "U5") (pin "2") (pinfunction "-IN_2") (pintype "input"))
    )
    (net (code "41") (name "Net-(U5A-OUT)") (class "Default")
      (node (ref "R7") (pin "2") (pinfunction "2_2") (pintype "passive"))
      (node (ref "R9") (pin "1") (pinfunction "1_1") (pintype "passive"))
      (node (ref "U5") (pin "1") (pinfunction "OUT_1") (pintype "output"))
    )
    (net (code "42") (name "Net-(U5B-+IN)") (class "Default")
      (node (ref "R8") (pin "2") (pinfunction "2_2") (pintype "passive"))
      (node (ref "R9") (pin "2") (pinfunction "2_2") (pintype "passive"))
      (node (ref "U5") (pin "5") (pinfunction "+IN_5") (pintype "input"))
    )
    (net (code "43") (name "Net-(U5B--IN)") (class "Default")
      (node (ref "R12") (pin "1") (pinfunction "1_1") (pintype "passive"))
      (node (ref "R13") (pin "1") (pinfunction "1_1") (pintype "passive"))
      (node (ref "U5") (pin "6") (pinfunction "-IN_6") (pintype "input"))
    )
    (net (code "44") (name "Net-(U5C--IN)") (class "Default")
      (node (ref "R16") (pin "2") (pinfunction "2_2") (pintype "passive"))
      (node (ref "R20") (pin "1") (pinfunction "1_1") (pintype "passive"))
      (node (ref "U5") (pin "9") (pinfunction "-IN_9") (pintype "input"))
    )
    (net (code "45") (name "Net-(U5C-OUT)") (class "Default")
      (node (ref "R20") (pin "2") (pinfunction "2_2") (pintype "passive"))
      (node (ref "R22") (pin "2") (pinfunction "2_2") (pintype "passive"))
      (node (ref "U5") (pin "8") (pinfunction "OUT_8") (pintype "output"))
    )
    (net (code "46") (name "Net-(U5D-+IN)") (class "Default")
      (node (ref "R21") (pin "2") (pinfunction "2_2") (pintype "passive"))
      (node (ref "R22") (pin "1") (pinfunction "1_1") (pintype "passive"))
      (node (ref "R23") (pin "1") (pinfunction "1_1") (pintype "passive"))
      (node (ref "U5") (pin "12") (pinfunction "+IN_12") (pintype "input"))
    )
    (net (code "47") (name "Net-(U5D-OUT)") (class "Default")
      (node (ref "LED1") (pin "A") (pinfunction "A_A") (pintype "passive"))
      (node (ref "U5") (pin "14") (pinfunction "OUT_14") (pintype "output"))
    )
    (net (code "48") (name "Net-(Z$102-INPUT)") (class "Default")
      (node (ref "R101") (pin "2") (pinfunction "2_2") (pintype "passive"))
      (node (ref "R102") (pin "2") (pinfunction "2_2") (pintype "passive"))
      (node (ref "Z$102") (pin "3") (pinfunction "INPUT_3") (pintype "bidirectional"))
    )
    (net (code "49") (name "Net-(Z$102-OUT1)") (class "Default")
      (node (ref "R104") (pin "1") (pinfunction "1_1") (pintype "passive"))
      (node (ref "Z$102") (pin "6") (pinfunction "OUT1_6") (pintype "bidirectional"))
    )
    (net (code "50") (name "Net-(Z$102-OUT2)") (class "Default")
      (node (ref "R105") (pin "1") (pinfunction "1_1") (pintype "passive"))
      (node (ref "Z$102") (pin "5") (pinfunction "OUT2_5") (pintype "bidirectional"))
    )
    (net (code "51") (name "REVERB_RETURN_F") (class "Default")
      (node (ref "JP102") (pin "2") (pinfunction "2_2") (pintype "passive"))
      (node (ref "U3") (pin "3") (pinfunction "+IN_3") (pintype "input"))
      (node (ref "X-FADE") (pin "P$2_SWITCH") (pinfunction "SWITCH_P$2_SWITCH") (pintype "passive"))
    )
    (net (code "52") (name "REVERB_SEND_B") (class "Default")
      (node (ref "C16") (pin "2") (pinfunction "2_2") (pintype "passive"))
      (node (ref "R101") (pin "1") (pinfunction "1_1") (pintype "passive"))
      (node (ref "R18") (pin "2") (pinfunction "2_2") (pintype "passive"))
      (node (ref "R19") (pin "2") (pinfunction "2_2") (pintype "passive"))
      (node (ref "U1") (pin "1") (pinfunction "OUT_1") (pintype "output"))
      (node (ref "U3") (pin "10") (pinfunction "+IN_10") (pintype "input"))
    )
    (net (code "53") (name "TRIM_F") (class "Default")
      (node (ref "C8") (pin "1") (pinfunction "1_1") (pintype "passive"))
      (node (ref "VR1") (pin "1") (pinfunction "1_1") (pintype "passive"))
    )
    (net (code "54") (name "VAC_AN_F") (class "Default")
      (node (ref "LED1") (pin "K") (pinfunction "C_K") (pintype "passive"))
      (node (ref "V$101") (pin "LED+") (pinfunction "LED+_LED+") (pintype "passive"))
    )
    (net (code "55") (name "VAC_CA_F") (class "Default")
      (node (ref "R24") (pin "1") (pinfunction "1_1") (pintype "passive"))
      (node (ref "U5") (pin "13") (pinfunction "-IN_13") (pintype "input"))
      (node (ref "V$101") (pin "LED-") (pinfunction "LED-_LED-") (pintype "passive"))
    )
    (net (code "56") (name "WET_F") (class "Default")
      (node (ref "IN_2") (pin "P$2_SWITCH") (pinfunction "SWITCH_P$2_SWITCH") (pintype "passive"))
      (node (ref "U3") (pin "1") (pinfunction "OUT_1") (pintype "output"))
      (node (ref "U3") (pin "2") (pinfunction "-IN_2") (pintype "input"))
      (node (ref "WET_OUT") (pin "P$1_TIP") (pinfunction "TIP_P$1_TIP") (pintype "passive"))
    )
    (net (code "57") (name "XFADE_F") (class "Default")
      (node (ref "U4") (pin "3") (pinfunction "+IN_3") (pintype "input"))
      (node (ref "X-FADE") (pin "P$1_TIP") (pinfunction "TIP_P$1_TIP") (pintype "passive"))
    )
    (net (code "58") (name "unconnected-(C14-Pad1)") (class "Default")
      (node (ref "C14") (pin "1") (pinfunction "1_1") (pintype "passive"))
    )
    (net (code "59") (name "unconnected-(CV-SWITCH-PadP$2_SWITCH)") (class "Default")
      (node (ref "CV") (pin "P$2_SWITCH") (pinfunction "SWITCH_P$2_SWITCH") (pintype "passive"))
    )
    (net (code "60") (name "unconnected-(IN_1-SWITCH-PadP$2_SWITCH)") (class "Default")
      (node (ref "IN_1") (pin "P$2_SWITCH") (pinfunction "SWITCH_P$2_SWITCH") (pintype "passive"))
    )
    (net (code "61") (name "unconnected-(J1-Pad1)") (class "Default")
      (node (ref "J1") (pin "1") (pinfunction "1_1") (pintype "passive"))
    )
    (net (code "62") (name "unconnected-(J1-Pad2)") (class "Default")
      (node (ref "J1") (pin "2") (pinfunction "2_2") (pintype "passive"))
    )
    (net (code "63") (name "unconnected-(MIX_OUT-SWITCH-PadP$2_SWITCH)") (class "Default")
      (node (ref "MIX_OUT") (pin "P$2_SWITCH") (pinfunction "SWITCH_P$2_SWITCH") (pintype "passive"))
    )
    (net (code "64") (name "unconnected-(WET_OUT-SWITCH-PadP$2_SWITCH)") (class "Default")
      (node (ref "WET_OUT") (pin "P$2_SWITCH") (pinfunction "SWITCH_P$2_SWITCH") (pintype "passive"))
    )
    (net (code "65") (name "unconnected-(X101-2-PadS@1)") (class "Default")
      (node (ref "X101") (pin "S@1") (pinfunction "2_S@1") (pintype "passive"))
    )
    (net (code "66") (name "unconnected-(X101-2-PadS@2)") (class "Default")
      (node (ref "X101") (pin "S@2") (pinfunction "2_S@2") (pintype "passive"))
    )
    (net (code "67") (name "unconnected-(X101-2-PadS@3)") (class "Default")
      (node (ref "X101") (pin "S@3") (pinfunction "2_S@3") (pintype "passive"))
    )
    (net (code "68") (name "unconnected-(X102-2-PadS@1)") (class "Default")
      (node (ref "X102") (pin "S@1") (pinfunction "2_S@1") (pintype "passive"))
    )
    (net (code "69") (name "unconnected-(X102-2-PadS@2)") (class "Default")
      (node (ref "X102") (pin "S@2") (pinfunction "2_S@2") (pintype "passive"))
    )
    (net (code "70") (name "unconnected-(X102-2-PadS@3)") (class "Default")
      (node (ref "X102") (pin "S@3") (pinfunction "2_S@3") (pintype "passive"))
    )
  )
)
